# SMT_Nixie_Board_HV5622.net
KiCad netlist of a schematic drawn in EAGLE
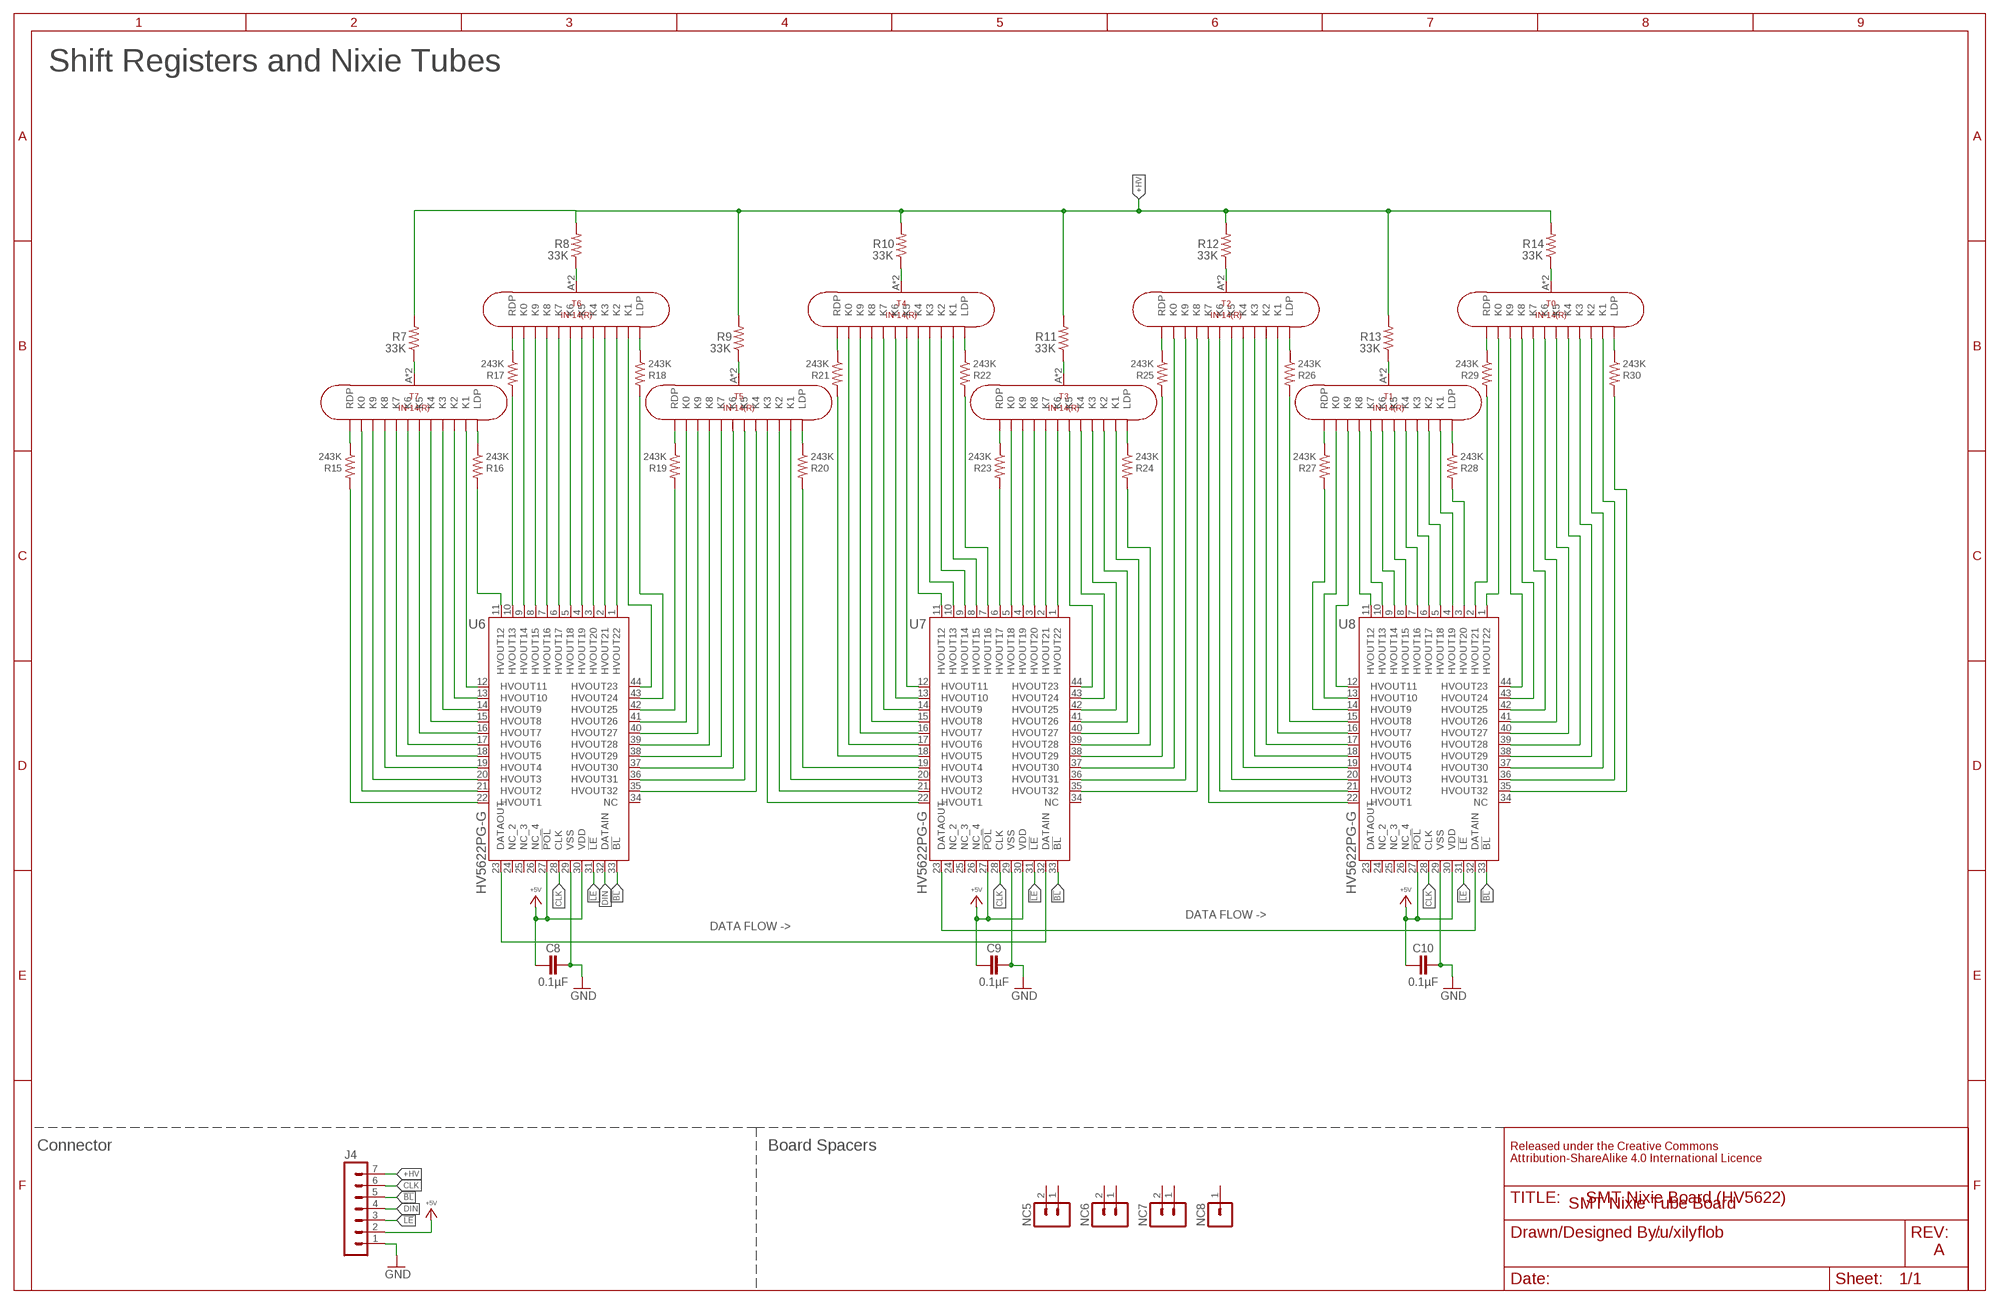
[diagram p0: schematic, sheet 1]

(export (version "E")
  (design (tool "Eeschema 10.0.6"))
  (components
    (comp (ref "C8")
      (value "0.1µF")
      (footprint "eagle-import:C0805")
      (libsource (lib "eagle-import") (part "C-EU"))
    )
    (comp (ref "C9")
      (value "0.1µF")
      (footprint "eagle-import:C0805")
      (libsource (lib "eagle-import") (part "C-EU"))
    )
    (comp (ref "C10")
      (value "0.1µF")
      (footprint "eagle-import:C0805")
      (libsource (lib "eagle-import") (part "C-EU"))
    )
    (comp (ref "J4")
      (value "1")
      (footprint "eagle-import:MA07")
      (libsource (lib "eagle-import") (part "MA07"))
    )
    (comp (ref "NC5")
      (value "MA02")
      (footprint "eagle-import:MA02")
      (libsource (lib "eagle-import") (part "MA02"))
    )
    (comp (ref "NC6")
      (value "MA02")
      (footprint "eagle-import:MA02")
      (libsource (lib "eagle-import") (part "MA02"))
    )
    (comp (ref "NC7")
      (value "MA02")
      (footprint "eagle-import:MA02")
      (libsource (lib "eagle-import") (part "MA02"))
    )
    (comp (ref "NC8")
      (value "MA01")
      (footprint "eagle-import:MA01")
      (libsource (lib "eagle-import") (part "MA01"))
    )
    (comp (ref "R7")
      (value "33K")
      (footprint "eagle-import:R2512")
      (libsource (lib "eagle-import") (part "R-US_R2512"))
    )
    (comp (ref "R8")
      (value "33K")
      (footprint "eagle-import:R2512")
      (libsource (lib "eagle-import") (part "R-US_R2512"))
    )
    (comp (ref "R9")
      (value "33K")
      (footprint "eagle-import:R2512")
      (libsource (lib "eagle-import") (part "R-US_R2512"))
    )
    (comp (ref "R10")
      (value "33K")
      (footprint "eagle-import:R2512")
      (libsource (lib "eagle-import") (part "R-US_R2512"))
    )
    (comp (ref "R11")
      (value "33K")
      (footprint "eagle-import:R2512")
      (libsource (lib "eagle-import") (part "R-US_R2512"))
    )
    (comp (ref "R12")
      (value "33K")
      (footprint "eagle-import:R2512")
      (libsource (lib "eagle-import") (part "R-US_R2512"))
    )
    (comp (ref "R13")
      (value "33K")
      (footprint "eagle-import:R2512")
      (libsource (lib "eagle-import") (part "R-US_R2512"))
    )
    (comp (ref "R14")
      (value "33K")
      (footprint "eagle-import:R2512")
      (libsource (lib "eagle-import") (part "R-US_R2512"))
    )
    (comp (ref "R15")
      (value "243K")
      (footprint "eagle-import:R2010")
      (libsource (lib "eagle-import") (part "R-US_R2010"))
    )
    (comp (ref "R16")
      (value "243K")
      (footprint "eagle-import:R2010")
      (libsource (lib "eagle-import") (part "R-US_R2010"))
    )
    (comp (ref "R17")
      (value "243K")
      (footprint "eagle-import:R2010")
      (libsource (lib "eagle-import") (part "R-US_R2010"))
    )
    (comp (ref "R18")
      (value "243K")
      (footprint "eagle-import:R2010")
      (libsource (lib "eagle-import") (part "R-US_R2010"))
    )
    (comp (ref "R19")
      (value "243K")
      (footprint "eagle-import:R2010")
      (libsource (lib "eagle-import") (part "R-US_R2010"))
    )
    (comp (ref "R20")
      (value "243K")
      (footprint "eagle-import:R2010")
      (libsource (lib "eagle-import") (part "R-US_R2010"))
    )
    (comp (ref "R21")
      (value "243K")
      (footprint "eagle-import:R2010")
      (libsource (lib "eagle-import") (part "R-US_R2010"))
    )
    (comp (ref "R22")
      (value "243K")
      (footprint "eagle-import:R2010")
      (libsource (lib "eagle-import") (part "R-US_R2010"))
    )
    (comp (ref "R23")
      (value "243K")
      (footprint "eagle-import:R2010")
      (libsource (lib "eagle-import") (part "R-US_R2010"))
    )
    (comp (ref "R24")
      (value "243K")
      (footprint "eagle-import:R2010")
      (libsource (lib "eagle-import") (part "R-US_R2010"))
    )
    (comp (ref "R25")
      (value "243K")
      (footprint "eagle-import:R2010")
      (libsource (lib "eagle-import") (part "R-US_R2010"))
    )
    (comp (ref "R26")
      (value "243K")
      (footprint "eagle-import:R2010")
      (libsource (lib "eagle-import") (part "R-US_R2010"))
    )
    (comp (ref "R27")
      (value "243K")
      (footprint "eagle-import:R2010")
      (libsource (lib "eagle-import") (part "R-US_R2010"))
    )
    (comp (ref "R28")
      (value "243K")
      (footprint "eagle-import:R2010")
      (libsource (lib "eagle-import") (part "R-US_R2010"))
    )
    (comp (ref "R29")
      (value "243K")
      (footprint "eagle-import:R2010")
      (libsource (lib "eagle-import") (part "R-US_R2010"))
    )
    (comp (ref "R30")
      (value "243K")
      (footprint "eagle-import:R2010")
      (libsource (lib "eagle-import") (part "R-US_R2010"))
    )
    (comp (ref "T0")
      (value "IN-14(R)")
      (footprint "eagle-import:IN-14_REVERSE")
      (libsource (lib "eagle-import") (part "IN-14(R)"))
    )
    (comp (ref "T1")
      (value "IN-14(R)")
      (footprint "eagle-import:IN-14_REVERSE")
      (libsource (lib "eagle-import") (part "IN-14(R)"))
    )
    (comp (ref "T2")
      (value "IN-14(R)")
      (footprint "eagle-import:IN-14_REVERSE")
      (libsource (lib "eagle-import") (part "IN-14(R)"))
    )
    (comp (ref "T3")
      (value "IN-14(R)")
      (footprint "eagle-import:IN-14_REVERSE")
      (libsource (lib "eagle-import") (part "IN-14(R)"))
    )
    (comp (ref "T4")
      (value "IN-14(R)")
      (footprint "eagle-import:IN-14_REVERSE")
      (libsource (lib "eagle-import") (part "IN-14(R)"))
    )
    (comp (ref "T5")
      (value "IN-14(R)")
      (footprint "eagle-import:IN-14_REVERSE")
      (libsource (lib "eagle-import") (part "IN-14(R)"))
    )
    (comp (ref "T6")
      (value "IN-14(R)")
      (footprint "eagle-import:IN-14_REVERSE")
      (libsource (lib "eagle-import") (part "IN-14(R)"))
    )
    (comp (ref "T7")
      (value "IN-14(R)")
      (footprint "eagle-import:IN-14_REVERSE")
      (libsource (lib "eagle-import") (part "IN-14(R)"))
    )
    (comp (ref "U6")
      (value "HV5622PG-G")
      (footprint "eagle-import:QFP-44")
      (fields (field (name "COPYRIGHT") "Copyright (C) 2018 Accelerated Designs. All rights reserved"))
      (libsource (lib "eagle-import") (part "HV5622PG-G"))
    )
    (comp (ref "U7")
      (value "HV5622PG-G")
      (footprint "eagle-import:QFP-44")
      (fields (field (name "COPYRIGHT") "Copyright (C) 2018 Accelerated Designs. All rights reserved"))
      (libsource (lib "eagle-import") (part "HV5622PG-G"))
    )
    (comp (ref "U8")
      (value "HV5622PG-G")
      (footprint "eagle-import:QFP-44")
      (fields (field (name "COPYRIGHT") "Copyright (C) 2018 Accelerated Designs. All rights reserved"))
      (libsource (lib "eagle-import") (part "HV5622PG-G"))
    )
  )
  (nets
    (net (code "1") (name "+5V") (class "Default")
      (node (ref "C10") (pin "1") (pinfunction "1_1") (pintype "passive"))
      (node (ref "C8") (pin "1") (pinfunction "1_1") (pintype "passive"))
      (node (ref "C9") (pin "1") (pinfunction "1_1") (pintype "passive"))
      (node (ref "J4") (pin "2") (pinfunction "2_2") (pintype "passive"))
      (node (ref "U6") (pin "27") (pinfunction "~{POL}_27") (pintype "passive"))
      (node (ref "U6") (pin "30") (pinfunction "VDD_30") (pintype "power_in"))
      (node (ref "U7") (pin "27") (pinfunction "~{POL}_27") (pintype "passive"))
      (node (ref "U7") (pin "30") (pinfunction "VDD_30") (pintype "power_in"))
      (node (ref "U8") (pin "27") (pinfunction "~{POL}_27") (pintype "passive"))
      (node (ref "U8") (pin "30") (pinfunction "VDD_30") (pintype "power_in"))
    )
    (net (code "2") (name "+HV") (class "Default")
      (node (ref "J4") (pin "7") (pinfunction "7_7") (pintype "passive"))
      (node (ref "R10") (pin "2") (pinfunction "2_2") (pintype "passive"))
      (node (ref "R11") (pin "2") (pinfunction "2_2") (pintype "passive"))
      (node (ref "R12") (pin "2") (pinfunction "2_2") (pintype "passive"))
      (node (ref "R13") (pin "2") (pinfunction "2_2") (pintype "passive"))
      (node (ref "R14") (pin "2") (pinfunction "2_2") (pintype "passive"))
      (node (ref "R7") (pin "2") (pinfunction "2_2") (pintype "passive"))
      (node (ref "R8") (pin "2") (pinfunction "2_2") (pintype "passive"))
      (node (ref "R9") (pin "2") (pinfunction "2_2") (pintype "passive"))
    )
    (net (code "3") (name "/~{BL}") (class "Default")
      (node (ref "J4") (pin "5") (pinfunction "5_5") (pintype "passive"))
      (node (ref "U6") (pin "33") (pinfunction "~{BL}_33") (pintype "passive"))
      (node (ref "U7") (pin "33") (pinfunction "~{BL}_33") (pintype "passive"))
      (node (ref "U8") (pin "33") (pinfunction "~{BL}_33") (pintype "passive"))
    )
    (net (code "4") (name "/~{LE}") (class "Default")
      (node (ref "J4") (pin "3") (pinfunction "3_3") (pintype "passive"))
      (node (ref "U6") (pin "31") (pinfunction "~{LE}_31") (pintype "input"))
      (node (ref "U7") (pin "31") (pinfunction "~{LE}_31") (pintype "input"))
      (node (ref "U8") (pin "31") (pinfunction "~{LE}_31") (pintype "input"))
    )
    (net (code "5") (name "CLK") (class "Default")
      (node (ref "J4") (pin "6") (pinfunction "6_6") (pintype "passive"))
      (node (ref "U6") (pin "28") (pinfunction "CLK_28") (pintype "input"))
      (node (ref "U7") (pin "28") (pinfunction "CLK_28") (pintype "input"))
      (node (ref "U8") (pin "28") (pinfunction "CLK_28") (pintype "input"))
    )
    (net (code "6") (name "DIN") (class "Default")
      (node (ref "J4") (pin "4") (pinfunction "4_4") (pintype "passive"))
      (node (ref "U6") (pin "32") (pinfunction "DATAIN_32") (pintype "input"))
    )
    (net (code "7") (name "GND") (class "Default")
      (node (ref "C10") (pin "2") (pinfunction "2_2") (pintype "passive"))
      (node (ref "C8") (pin "2") (pinfunction "2_2") (pintype "passive"))
      (node (ref "C9") (pin "2") (pinfunction "2_2") (pintype "passive"))
      (node (ref "J4") (pin "1") (pinfunction "1_1") (pintype "passive"))
      (node (ref "U6") (pin "29") (pinfunction "VSS_29") (pintype "power_in"))
      (node (ref "U7") (pin "29") (pinfunction "VSS_29") (pintype "power_in"))
      (node (ref "U8") (pin "29") (pinfunction "VSS_29") (pintype "power_in"))
    )
    (net (code "8") (name "Net-(R7-Pad1)") (class "Default")
      (node (ref "R7") (pin "1") (pinfunction "1_1") (pintype "passive"))
      (node (ref "T7") (pin "A") (pinfunction "A_A") (pintype "output"))
      (node (ref "T7") (pin "A_1") (pinfunction "A_A_1") (pintype "output"))
    )
    (net (code "9") (name "Net-(R8-Pad1)") (class "Default")
      (node (ref "R8") (pin "1") (pinfunction "1_1") (pintype "passive"))
      (node (ref "T6") (pin "A") (pinfunction "A_A") (pintype "output"))
      (node (ref "T6") (pin "A_1") (pinfunction "A_A_1") (pintype "output"))
    )
    (net (code "10") (name "Net-(R9-Pad1)") (class "Default")
      (node (ref "R9") (pin "1") (pinfunction "1_1") (pintype "passive"))
      (node (ref "T5") (pin "A") (pinfunction "A_A") (pintype "output"))
      (node (ref "T5") (pin "A_1") (pinfunction "A_A_1") (pintype "output"))
    )
    (net (code "11") (name "Net-(R10-Pad1)") (class "Default")
      (node (ref "R10") (pin "1") (pinfunction "1_1") (pintype "passive"))
      (node (ref "T4") (pin "A") (pinfunction "A_A") (pintype "output"))
      (node (ref "T4") (pin "A_1") (pinfunction "A_A_1") (pintype "output"))
    )
    (net (code "12") (name "Net-(R11-Pad1)") (class "Default")
      (node (ref "R11") (pin "1") (pinfunction "1_1") (pintype "passive"))
      (node (ref "T3") (pin "A") (pinfunction "A_A") (pintype "output"))
      (node (ref "T3") (pin "A_1") (pinfunction "A_A_1") (pintype "output"))
    )
    (net (code "13") (name "Net-(R12-Pad1)") (class "Default")
      (node (ref "R12") (pin "1") (pinfunction "1_1") (pintype "passive"))
      (node (ref "T2") (pin "A") (pinfunction "A_A") (pintype "output"))
      (node (ref "T2") (pin "A_1") (pinfunction "A_A_1") (pintype "output"))
    )
    (net (code "14") (name "Net-(R13-Pad1)") (class "Default")
      (node (ref "R13") (pin "1") (pinfunction "1_1") (pintype "passive"))
      (node (ref "T1") (pin "A") (pinfunction "A_A") (pintype "output"))
      (node (ref "T1") (pin "A_1") (pinfunction "A_A_1") (pintype "output"))
    )
    (net (code "15") (name "Net-(R14-Pad1)") (class "Default")
      (node (ref "R14") (pin "1") (pinfunction "1_1") (pintype "passive"))
      (node (ref "T0") (pin "A") (pinfunction "A_A") (pintype "output"))
      (node (ref "T0") (pin "A_1") (pinfunction "A_A_1") (pintype "output"))
    )
    (net (code "16") (name "Net-(R15-Pad1)") (class "Default")
      (node (ref "R15") (pin "1") (pinfunction "1_1") (pintype "passive"))
      (node (ref "T7") (pin "RDP") (pinfunction "RDP_RDP") (pintype "input"))
      (node (ref "T7") (pin "RDP_1") (pinfunction "RDP_RDP_1") (pintype "input"))
    )
    (net (code "17") (name "Net-(R16-Pad1)") (class "Default")
      (node (ref "R16") (pin "1") (pinfunction "1_1") (pintype "passive"))
      (node (ref "T7") (pin "LDP") (pinfunction "LDP_LDP") (pintype "input"))
      (node (ref "T7") (pin "LDP_1") (pinfunction "LDP_LDP_1") (pintype "input"))
    )
    (net (code "18") (name "Net-(R17-Pad1)") (class "Default")
      (node (ref "R17") (pin "1") (pinfunction "1_1") (pintype "passive"))
      (node (ref "T6") (pin "RDP") (pinfunction "RDP_RDP") (pintype "input"))
      (node (ref "T6") (pin "RDP_1") (pinfunction "RDP_RDP_1") (pintype "input"))
    )
    (net (code "19") (name "Net-(R18-Pad1)") (class "Default")
      (node (ref "R18") (pin "1") (pinfunction "1_1") (pintype "passive"))
      (node (ref "T6") (pin "LDP") (pinfunction "LDP_LDP") (pintype "input"))
      (node (ref "T6") (pin "LDP_1") (pinfunction "LDP_LDP_1") (pintype "input"))
    )
    (net (code "20") (name "Net-(R19-Pad1)") (class "Default")
      (node (ref "R19") (pin "1") (pinfunction "1_1") (pintype "passive"))
      (node (ref "T5") (pin "RDP") (pinfunction "RDP_RDP") (pintype "input"))
      (node (ref "T5") (pin "RDP_1") (pinfunction "RDP_RDP_1") (pintype "input"))
    )
    (net (code "21") (name "Net-(R20-Pad1)") (class "Default")
      (node (ref "R20") (pin "1") (pinfunction "1_1") (pintype "passive"))
      (node (ref "T5") (pin "LDP") (pinfunction "LDP_LDP") (pintype "input"))
      (node (ref "T5") (pin "LDP_1") (pinfunction "LDP_LDP_1") (pintype "input"))
    )
    (net (code "22") (name "Net-(R21-Pad1)") (class "Default")
      (node (ref "R21") (pin "1") (pinfunction "1_1") (pintype "passive"))
      (node (ref "T4") (pin "RDP") (pinfunction "RDP_RDP") (pintype "input"))
      (node (ref "T4") (pin "RDP_1") (pinfunction "RDP_RDP_1") (pintype "input"))
    )
    (net (code "23") (name "Net-(R22-Pad1)") (class "Default")
      (node (ref "R22") (pin "1") (pinfunction "1_1") (pintype "passive"))
      (node (ref "T4") (pin "LDP") (pinfunction "LDP_LDP") (pintype "input"))
      (node (ref "T4") (pin "LDP_1") (pinfunction "LDP_LDP_1") (pintype "input"))
    )
    (net (code "24") (name "Net-(R23-Pad1)") (class "Default")
      (node (ref "R23") (pin "1") (pinfunction "1_1") (pintype "passive"))
      (node (ref "T3") (pin "RDP") (pinfunction "RDP_RDP") (pintype "input"))
      (node (ref "T3") (pin "RDP_1") (pinfunction "RDP_RDP_1") (pintype "input"))
    )
    (net (code "25") (name "Net-(R24-Pad1)") (class "Default")
      (node (ref "R24") (pin "1") (pinfunction "1_1") (pintype "passive"))
      (node (ref "T3") (pin "LDP") (pinfunction "LDP_LDP") (pintype "input"))
      (node (ref "T3") (pin "LDP_1") (pinfunction "LDP_LDP_1") (pintype "input"))
    )
    (net (code "26") (name "Net-(R25-Pad1)") (class "Default")
      (node (ref "R25") (pin "1") (pinfunction "1_1") (pintype "passive"))
      (node (ref "T2") (pin "RDP") (pinfunction "RDP_RDP") (pintype "input"))
      (node (ref "T2") (pin "RDP_1") (pinfunction "RDP_RDP_1") (pintype "input"))
    )
    (net (code "27") (name "Net-(R26-Pad1)") (class "Default")
      (node (ref "R26") (pin "1") (pinfunction "1_1") (pintype "passive"))
      (node (ref "T2") (pin "LDP") (pinfunction "LDP_LDP") (pintype "input"))
      (node (ref "T2") (pin "LDP_1") (pinfunction "LDP_LDP_1") (pintype "input"))
    )
    (net (code "28") (name "Net-(R27-Pad1)") (class "Default")
      (node (ref "R27") (pin "1") (pinfunction "1_1") (pintype "passive"))
      (node (ref "T1") (pin "RDP") (pinfunction "RDP_RDP") (pintype "input"))
      (node (ref "T1") (pin "RDP_1") (pinfunction "RDP_RDP_1") (pintype "input"))
    )
    (net (code "29") (name "Net-(R28-Pad1)") (class "Default")
      (node (ref "R28") (pin "1") (pinfunction "1_1") (pintype "passive"))
      (node (ref "T1") (pin "LDP") (pinfunction "LDP_LDP") (pintype "input"))
      (node (ref "T1") (pin "LDP_1") (pinfunction "LDP_LDP_1") (pintype "input"))
    )
    (net (code "30") (name "Net-(R29-Pad1)") (class "Default")
      (node (ref "R29") (pin "1") (pinfunction "1_1") (pintype "passive"))
      (node (ref "T0") (pin "RDP") (pinfunction "RDP_RDP") (pintype "input"))
      (node (ref "T0") (pin "RDP_1") (pinfunction "RDP_RDP_1") (pintype "input"))
    )
    (net (code "31") (name "Net-(R30-Pad1)") (class "Default")
      (node (ref "R30") (pin "1") (pinfunction "1_1") (pintype "passive"))
      (node (ref "T0") (pin "LDP") (pinfunction "LDP_LDP") (pintype "input"))
      (node (ref "T0") (pin "LDP_1") (pinfunction "LDP_LDP_1") (pintype "input"))
    )
    (net (code "32") (name "Net-(U6-DATAOUT)") (class "Default")
      (node (ref "U6") (pin "23") (pinfunction "DATAOUT_23") (pintype "output"))
      (node (ref "U7") (pin "32") (pinfunction "DATAIN_32") (pintype "input"))
    )
    (net (code "33") (name "Net-(U6-HVOUT1)") (class "Default")
      (node (ref "R15") (pin "2") (pinfunction "2_2") (pintype "passive"))
      (node (ref "U6") (pin "22") (pinfunction "HVOUT1_22") (pintype "output"))
    )
    (net (code "34") (name "Net-(U6-HVOUT2)") (class "Default")
      (node (ref "T7") (pin "K0") (pinfunction "K0_K0") (pintype "input"))
      (node (ref "T7") (pin "K0_1") (pinfunction "K0_K0_1") (pintype "input"))
      (node (ref "U6") (pin "21") (pinfunction "HVOUT2_21") (pintype "output"))
    )
    (net (code "35") (name "Net-(U6-HVOUT3)") (class "Default")
      (node (ref "T7") (pin "K9") (pinfunction "K9_K9") (pintype "input"))
      (node (ref "T7") (pin "K9_1") (pinfunction "K9_K9_1") (pintype "input"))
      (node (ref "U6") (pin "20") (pinfunction "HVOUT3_20") (pintype "output"))
    )
    (net (code "36") (name "Net-(U6-HVOUT4)") (class "Default")
      (node (ref "T7") (pin "K8") (pinfunction "K8_K8") (pintype "input"))
      (node (ref "T7") (pin "K8_1") (pinfunction "K8_K8_1") (pintype "input"))
      (node (ref "U6") (pin "19") (pinfunction "HVOUT4_19") (pintype "output"))
    )
    (net (code "37") (name "Net-(U6-HVOUT5)") (class "Default")
      (node (ref "T7") (pin "K7") (pinfunction "K7_K7") (pintype "input"))
      (node (ref "T7") (pin "K7_1") (pinfunction "K7_K7_1") (pintype "input"))
      (node (ref "U6") (pin "18") (pinfunction "HVOUT5_18") (pintype "output"))
    )
    (net (code "38") (name "Net-(U6-HVOUT6)") (class "Default")
      (node (ref "T7") (pin "K6") (pinfunction "K6_K6") (pintype "input"))
      (node (ref "T7") (pin "K6_1") (pinfunction "K6_K6_1") (pintype "input"))
      (node (ref "U6") (pin "17") (pinfunction "HVOUT6_17") (pintype "output"))
    )
    (net (code "39") (name "Net-(U6-HVOUT7)") (class "Default")
      (node (ref "T7") (pin "K5") (pinfunction "K5_K5") (pintype "input"))
      (node (ref "T7") (pin "K5_1") (pinfunction "K5_K5_1") (pintype "input"))
      (node (ref "U6") (pin "16") (pinfunction "HVOUT7_16") (pintype "output"))
    )
    (net (code "40") (name "Net-(U6-HVOUT8)") (class "Default")
      (node (ref "T7") (pin "K4") (pinfunction "K4_K4") (pintype "input"))
      (node (ref "T7") (pin "K4_1") (pinfunction "K4_K4_1") (pintype "input"))
      (node (ref "U6") (pin "15") (pinfunction "HVOUT8_15") (pintype "output"))
    )
    (net (code "41") (name "Net-(U6-HVOUT9)") (class "Default")
      (node (ref "T7") (pin "K3") (pinfunction "K3_K3") (pintype "input"))
      (node (ref "T7") (pin "K3_1") (pinfunction "K3_K3_1") (pintype "input"))
      (node (ref "U6") (pin "14") (pinfunction "HVOUT9_14") (pintype "output"))
    )
    (net (code "42") (name "Net-(U6-HVOUT10)") (class "Default")
      (node (ref "T7") (pin "K2") (pinfunction "K2_K2") (pintype "input"))
      (node (ref "T7") (pin "K2_1") (pinfunction "K2_K2_1") (pintype "input"))
      (node (ref "U6") (pin "13") (pinfunction "HVOUT10_13") (pintype "output"))
    )
    (net (code "43") (name "Net-(U6-HVOUT11)") (class "Default")
      (node (ref "T7") (pin "K1") (pinfunction "K1_K1") (pintype "input"))
      (node (ref "T7") (pin "K1_1") (pinfunction "K1_K1_1") (pintype "input"))
      (node (ref "U6") (pin "12") (pinfunction "HVOUT11_12") (pintype "output"))
    )
    (net (code "44") (name "Net-(U6-HVOUT12)") (class "Default")
      (node (ref "R16") (pin "2") (pinfunction "2_2") (pintype "passive"))
      (node (ref "U6") (pin "11") (pinfunction "HVOUT12_11") (pintype "output"))
    )
    (net (code "45") (name "Net-(U6-HVOUT13)") (class "Default")
      (node (ref "R17") (pin "2") (pinfunction "2_2") (pintype "passive"))
      (node (ref "U6") (pin "10") (pinfunction "HVOUT13_10") (pintype "output"))
    )
    (net (code "46") (name "Net-(U6-HVOUT14)") (class "Default")
      (node (ref "T6") (pin "K0") (pinfunction "K0_K0") (pintype "input"))
      (node (ref "T6") (pin "K0_1") (pinfunction "K0_K0_1") (pintype "input"))
      (node (ref "U6") (pin "9") (pinfunction "HVOUT14_9") (pintype "output"))
    )
    (net (code "47") (name "Net-(U6-HVOUT15)") (class "Default")
      (node (ref "T6") (pin "K9") (pinfunction "K9_K9") (pintype "input"))
      (node (ref "T6") (pin "K9_1") (pinfunction "K9_K9_1") (pintype "input"))
      (node (ref "U6") (pin "8") (pinfunction "HVOUT15_8") (pintype "output"))
    )
    (net (code "48") (name "Net-(U6-HVOUT16)") (class "Default")
      (node (ref "T6") (pin "K8") (pinfunction "K8_K8") (pintype "input"))
      (node (ref "T6") (pin "K8_1") (pinfunction "K8_K8_1") (pintype "input"))
      (node (ref "U6") (pin "7") (pinfunction "HVOUT16_7") (pintype "output"))
    )
    (net (code "49") (name "Net-(U6-HVOUT17)") (class "Default")
      (node (ref "T6") (pin "K7") (pinfunction "K7_K7") (pintype "input"))
      (node (ref "T6") (pin "K7_1") (pinfunction "K7_K7_1") (pintype "input"))
      (node (ref "U6") (pin "6") (pinfunction "HVOUT17_6") (pintype "output"))
    )
    (net (code "50") (name "Net-(U6-HVOUT18)") (class "Default")
      (node (ref "T6") (pin "K6") (pinfunction "K6_K6") (pintype "input"))
      (node (ref "T6") (pin "K6_1") (pinfunction "K6_K6_1") (pintype "input"))
      (node (ref "U6") (pin "5") (pinfunction "HVOUT18_5") (pintype "output"))
    )
    (net (code "51") (name "Net-(U6-HVOUT19)") (class "Default")
      (node (ref "T6") (pin "K5") (pinfunction "K5_K5") (pintype "input"))
      (node (ref "T6") (pin "K5_1") (pinfunction "K5_K5_1") (pintype "input"))
      (node (ref "U6") (pin "4") (pinfunction "HVOUT19_4") (pintype "output"))
    )
    (net (code "52") (name "Net-(U6-HVOUT20)") (class "Default")
      (node (ref "T6") (pin "K4") (pinfunction "K4_K4") (pintype "input"))
      (node (ref "T6") (pin "K4_1") (pinfunction "K4_K4_1") (pintype "input"))
      (node (ref "U6") (pin "3") (pinfunction "HVOUT20_3") (pintype "output"))
    )
    (net (code "53") (name "Net-(U6-HVOUT21)") (class "Default")
      (node (ref "T6") (pin "K3") (pinfunction "K3_K3") (pintype "input"))
      (node (ref "T6") (pin "K3_1") (pinfunction "K3_K3_1") (pintype "input"))
      (node (ref "U6") (pin "2") (pinfunction "HVOUT21_2") (pintype "output"))
    )
    (net (code "54") (name "Net-(U6-HVOUT22)") (class "Default")
      (node (ref "T6") (pin "K2") (pinfunction "K2_K2") (pintype "input"))
      (node (ref "T6") (pin "K2_1") (pinfunction "K2_K2_1") (pintype "input"))
      (node (ref "U6") (pin "1") (pinfunction "HVOUT22_1") (pintype "output"))
    )
    (net (code "55") (name "Net-(U6-HVOUT23)") (class "Default")
      (node (ref "T6") (pin "K1") (pinfunction "K1_K1") (pintype "input"))
      (node (ref "T6") (pin "K1_1") (pinfunction "K1_K1_1") (pintype "input"))
      (node (ref "U6") (pin "44") (pinfunction "HVOUT23_44") (pintype "output"))
    )
    (net (code "56") (name "Net-(U6-HVOUT24)") (class "Default")
      (node (ref "R18") (pin "2") (pinfunction "2_2") (pintype "passive"))
      (node (ref "U6") (pin "43") (pinfunction "HVOUT24_43") (pintype "output"))
    )
    (net (code "57") (name "Net-(U6-HVOUT25)") (class "Default")
      (node (ref "R19") (pin "2") (pinfunction "2_2") (pintype "passive"))
      (node (ref "U6") (pin "42") (pinfunction "HVOUT25_42") (pintype "output"))
    )
    (net (code "58") (name "Net-(U6-HVOUT26)") (class "Default")
      (node (ref "T5") (pin "K0") (pinfunction "K0_K0") (pintype "input"))
      (node (ref "T5") (pin "K0_1") (pinfunction "K0_K0_1") (pintype "input"))
      (node (ref "U6") (pin "41") (pinfunction "HVOUT26_41") (pintype "output"))
    )
    (net (code "59") (name "Net-(U6-HVOUT27)") (class "Default")
      (node (ref "T5") (pin "K9") (pinfunction "K9_K9") (pintype "input"))
      (node (ref "T5") (pin "K9_1") (pinfunction "K9_K9_1") (pintype "input"))
      (node (ref "U6") (pin "40") (pinfunction "HVOUT27_40") (pintype "output"))
    )
    (net (code "60") (name "Net-(U6-HVOUT28)") (class "Default")
      (node (ref "T5") (pin "K8") (pinfunction "K8_K8") (pintype "input"))
      (node (ref "T5") (pin "K8_1") (pinfunction "K8_K8_1") (pintype "input"))
      (node (ref "U6") (pin "39") (pinfunction "HVOUT28_39") (pintype "output"))
    )
    (net (code "61") (name "Net-(U6-HVOUT29)") (class "Default")
      (node (ref "T5") (pin "K7") (pinfunction "K7_K7") (pintype "input"))
      (node (ref "T5") (pin "K7_1") (pinfunction "K7_K7_1") (pintype "input"))
      (node (ref "U6") (pin "38") (pinfunction "HVOUT29_38") (pintype "output"))
    )
    (net (code "62") (name "Net-(U6-HVOUT30)") (class "Default")
      (node (ref "T5") (pin "K6") (pinfunction "K6_K6") (pintype "input"))
      (node (ref "T5") (pin "K6_1") (pinfunction "K6_K6_1") (pintype "input"))
      (node (ref "U6") (pin "37") (pinfunction "HVOUT30_37") (pintype "output"))
    )
    (net (code "63") (name "Net-(U6-HVOUT31)") (class "Default")
      (node (ref "T5") (pin "K5") (pinfunction "K5_K5") (pintype "input"))
      (node (ref "T5") (pin "K5_1") (pinfunction "K5_K5_1") (pintype "input"))
      (node (ref "U6") (pin "36") (pinfunction "HVOUT31_36") (pintype "output"))
    )
    (net (code "64") (name "Net-(U6-HVOUT32)") (class "Default")
      (node (ref "T5") (pin "K4") (pinfunction "K4_K4") (pintype "input"))
      (node (ref "T5") (pin "K4_1") (pinfunction "K4_K4_1") (pintype "input"))
      (node (ref "U6") (pin "35") (pinfunction "HVOUT32_35") (pintype "output"))
    )
    (net (code "65") (name "Net-(U7-DATAOUT)") (class "Default")
      (node (ref "U7") (pin "23") (pinfunction "DATAOUT_23") (pintype "output"))
      (node (ref "U8") (pin "32") (pinfunction "DATAIN_32") (pintype "input"))
    )
    (net (code "66") (name "Net-(U7-HVOUT1)") (class "Default")
      (node (ref "T5") (pin "K3") (pinfunction "K3_K3") (pintype "input"))
      (node (ref "T5") (pin "K3_1") (pinfunction "K3_K3_1") (pintype "input"))
      (node (ref "U7") (pin "22") (pinfunction "HVOUT1_22") (pintype "output"))
    )
    (net (code "67") (name "Net-(U7-HVOUT2)") (class "Default")
      (node (ref "T5") (pin "K2") (pinfunction "K2_K2") (pintype "input"))
      (node (ref "T5") (pin "K2_1") (pinfunction "K2_K2_1") (pintype "input"))
      (node (ref "U7") (pin "21") (pinfunction "HVOUT2_21") (pintype "output"))
    )
    (net (code "68") (name "Net-(U7-HVOUT3)") (class "Default")
      (node (ref "T5") (pin "K1") (pinfunction "K1_K1") (pintype "input"))
      (node (ref "T5") (pin "K1_1") (pinfunction "K1_K1_1") (pintype "input"))
      (node (ref "U7") (pin "20") (pinfunction "HVOUT3_20") (pintype "output"))
    )
    (net (code "69") (name "Net-(U7-HVOUT4)") (class "Default")
      (node (ref "R20") (pin "2") (pinfunction "2_2") (pintype "passive"))
      (node (ref "U7") (pin "19") (pinfunction "HVOUT4_19") (pintype "output"))
    )
    (net (code "70") (name "Net-(U7-HVOUT5)") (class "Default")
      (node (ref "R21") (pin "2") (pinfunction "2_2") (pintype "passive"))
      (node (ref "U7") (pin "18") (pinfunction "HVOUT5_18") (pintype "output"))
    )
    (net (code "71") (name "Net-(U7-HVOUT6)") (class "Default")
      (node (ref "T4") (pin "K0") (pinfunction "K0_K0") (pintype "input"))
      (node (ref "T4") (pin "K0_1") (pinfunction "K0_K0_1") (pintype "input"))
      (node (ref "U7") (pin "17") (pinfunction "HVOUT6_17") (pintype "output"))
    )
    (net (code "72") (name "Net-(U7-HVOUT7)") (class "Default")
      (node (ref "T4") (pin "K9") (pinfunction "K9_K9") (pintype "input"))
      (node (ref "T4") (pin "K9_1") (pinfunction "K9_K9_1") (pintype "input"))
      (node (ref "U7") (pin "16") (pinfunction "HVOUT7_16") (pintype "output"))
    )
    (net (code "73") (name "Net-(U7-HVOUT8)") (class "Default")
      (node (ref "T4") (pin "K8") (pinfunction "K8_K8") (pintype "input"))
      (node (ref "T4") (pin "K8_1") (pinfunction "K8_K8_1") (pintype "input"))
      (node (ref "U7") (pin "15") (pinfunction "HVOUT8_15") (pintype "output"))
    )
    (net (code "74") (name "Net-(U7-HVOUT9)") (class "Default")
      (node (ref "T4") (pin "K7") (pinfunction "K7_K7") (pintype "input"))
      (node (ref "T4") (pin "K7_1") (pinfunction "K7_K7_1") (pintype "input"))
      (node (ref "U7") (pin "14") (pinfunction "HVOUT9_14") (pintype "output"))
    )
    (net (code "75") (name "Net-(U7-HVOUT10)") (class "Default")
      (node (ref "T4") (pin "K6") (pinfunction "K6_K6") (pintype "input"))
      (node (ref "T4") (pin "K6_1") (pinfunction "K6_K6_1") (pintype "input"))
      (node (ref "U7") (pin "13") (pinfunction "HVOUT10_13") (pintype "output"))
    )
    (net (code "76") (name "Net-(U7-HVOUT11)") (class "Default")
      (node (ref "T4") (pin "K5") (pinfunction "K5_K5") (pintype "input"))
      (node (ref "T4") (pin "K5_1") (pinfunction "K5_K5_1") (pintype "input"))
      (node (ref "U7") (pin "12") (pinfunction "HVOUT11_12") (pintype "output"))
    )
    (net (code "77") (name "Net-(U7-HVOUT12)") (class "Default")
      (node (ref "T4") (pin "K4") (pinfunction "K4_K4") (pintype "input"))
      (node (ref "T4") (pin "K4_1") (pinfunction "K4_K4_1") (pintype "input"))
      (node (ref "U7") (pin "11") (pinfunction "HVOUT12_11") (pintype "output"))
    )
    (net (code "78") (name "Net-(U7-HVOUT13)") (class "Default")
      (node (ref "T4") (pin "K3") (pinfunction "K3_K3") (pintype "input"))
      (node (ref "T4") (pin "K3_1") (pinfunction "K3_K3_1") (pintype "input"))
      (node (ref "U7") (pin "10") (pinfunction "HVOUT13_10") (pintype "output"))
    )
    (net (code "79") (name "Net-(U7-HVOUT14)") (class "Default")
      (node (ref "T4") (pin "K2") (pinfunction "K2_K2") (pintype "input"))
      (node (ref "T4") (pin "K2_1") (pinfunction "K2_K2_1") (pintype "input"))
      (node (ref "U7") (pin "9") (pinfunction "HVOUT14_9") (pintype "output"))
    )
    (net (code "80") (name "Net-(U7-HVOUT15)") (class "Default")
      (node (ref "T4") (pin "K1") (pinfunction "K1_K1") (pintype "input"))
      (node (ref "T4") (pin "K1_1") (pinfunction "K1_K1_1") (pintype "input"))
      (node (ref "U7") (pin "8") (pinfunction "HVOUT15_8") (pintype "output"))
    )
    (net (code "81") (name "Net-(U7-HVOUT16)") (class "Default")
      (node (ref "R22") (pin "2") (pinfunction "2_2") (pintype "passive"))
      (node (ref "U7") (pin "7") (pinfunction "HVOUT16_7") (pintype "output"))
    )
    (net (code "82") (name "Net-(U7-HVOUT17)") (class "Default")
      (node (ref "R23") (pin "2") (pinfunction "2_2") (pintype "passive"))
      (node (ref "U7") (pin "6") (pinfunction "HVOUT17_6") (pintype "output"))
    )
    (net (code "83") (name "Net-(U7-HVOUT18)") (class "Default")
      (node (ref "T3") (pin "K0") (pinfunction "K0_K0") (pintype "input"))
      (node (ref "T3") (pin "K0_1") (pinfunction "K0_K0_1") (pintype "input"))
      (node (ref "U7") (pin "5") (pinfunction "HVOUT18_5") (pintype "output"))
    )
    (net (code "84") (name "Net-(U7-HVOUT19)") (class "Default")
      (node (ref "T3") (pin "K9") (pinfunction "K9_K9") (pintype "input"))
      (node (ref "T3") (pin "K9_1") (pinfunction "K9_K9_1") (pintype "input"))
      (node (ref "U7") (pin "4") (pinfunction "HVOUT19_4") (pintype "output"))
    )
    (net (code "85") (name "Net-(U7-HVOUT20)") (class "Default")
      (node (ref "T3") (pin "K8") (pinfunction "K8_K8") (pintype "input"))
      (node (ref "T3") (pin "K8_1") (pinfunction "K8_K8_1") (pintype "input"))
      (node (ref "U7") (pin "3") (pinfunction "HVOUT20_3") (pintype "output"))
    )
    (net (code "86") (name "Net-(U7-HVOUT21)") (class "Default")
      (node (ref "T3") (pin "K7") (pinfunction "K7_K7") (pintype "input"))
      (node (ref "T3") (pin "K7_1") (pinfunction "K7_K7_1") (pintype "input"))
      (node (ref "U7") (pin "2") (pinfunction "HVOUT21_2") (pintype "output"))
    )
    (net (code "87") (name "Net-(U7-HVOUT22)") (class "Default")
      (node (ref "T3") (pin "K6") (pinfunction "K6_K6") (pintype "input"))
      (node (ref "T3") (pin "K6_1") (pinfunction "K6_K6_1") (pintype "input"))
      (node (ref "U7") (pin "1") (pinfunction "HVOUT22_1") (pintype "output"))
    )
    (net (code "88") (name "Net-(U7-HVOUT23)") (class "Default")
      (node (ref "T3") (pin "K5") (pinfunction "K5_K5") (pintype "input"))
      (node (ref "T3") (pin "K5_1") (pinfunction "K5_K5_1") (pintype "input"))
      (node (ref "U7") (pin "44") (pinfunction "HVOUT23_44") (pintype "output"))
    )
    (net (code "89") (name "Net-(U7-HVOUT24)") (class "Default")
      (node (ref "T3") (pin "K4") (pinfunction "K4_K4") (pintype "input"))
      (node (ref "T3") (pin "K4_1") (pinfunction "K4_K4_1") (pintype "input"))
      (node (ref "U7") (pin "43") (pinfunction "HVOUT24_43") (pintype "output"))
    )
    (net (code "90") (name "Net-(U7-HVOUT25)") (class "Default")
      (node (ref "T3") (pin "K3") (pinfunction "K3_K3") (pintype "input"))
      (node (ref "T3") (pin "K3_1") (pinfunction "K3_K3_1") (pintype "input"))
      (node (ref "U7") (pin "42") (pinfunction "HVOUT25_42") (pintype "output"))
    )
    (net (code "91") (name "Net-(U7-HVOUT26)") (class "Default")
      (node (ref "T3") (pin "K2") (pinfunction "K2_K2") (pintype "input"))
      (node (ref "T3") (pin "K2_1") (pinfunction "K2_K2_1") (pintype "input"))
      (node (ref "U7") (pin "41") (pinfunction "HVOUT26_41") (pintype "output"))
    )
    (net (code "92") (name "Net-(U7-HVOUT27)") (class "Default")
      (node (ref "T3") (pin "K1") (pinfunction "K1_K1") (pintype "input"))
      (node (ref "T3") (pin "K1_1") (pinfunction "K1_K1_1") (pintype "input"))
      (node (ref "U7") (pin "40") (pinfunction "HVOUT27_40") (pintype "output"))
    )
    (net (code "93") (name "Net-(U7-HVOUT28)") (class "Default")
      (node (ref "R24") (pin "2") (pinfunction "2_2") (pintype "passive"))
      (node (ref "U7") (pin "39") (pinfunction "HVOUT28_39") (pintype "output"))
    )
    (net (code "94") (name "Net-(U7-HVOUT29)") (class "Default")
      (node (ref "R25") (pin "2") (pinfunction "2_2") (pintype "passive"))
      (node (ref "U7") (pin "38") (pinfunction "HVOUT29_38") (pintype "output"))
    )
    (net (code "95") (name "Net-(U7-HVOUT30)") (class "Default")
      (node (ref "T2") (pin "K0") (pinfunction "K0_K0") (pintype "input"))
      (node (ref "T2") (pin "K0_1") (pinfunction "K0_K0_1") (pintype "input"))
      (node (ref "U7") (pin "37") (pinfunction "HVOUT30_37") (pintype "output"))
    )
    (net (code "96") (name "Net-(U7-HVOUT31)") (class "Default")
      (node (ref "T2") (pin "K9") (pinfunction "K9_K9") (pintype "input"))
      (node (ref "T2") (pin "K9_1") (pinfunction "K9_K9_1") (pintype "input"))
      (node (ref "U7") (pin "36") (pinfunction "HVOUT31_36") (pintype "output"))
    )
    (net (code "97") (name "Net-(U7-HVOUT32)") (class "Default")
      (node (ref "T2") (pin "K8") (pinfunction "K8_K8") (pintype "input"))
      (node (ref "T2") (pin "K8_1") (pinfunction "K8_K8_1") (pintype "input"))
      (node (ref "U7") (pin "35") (pinfunction "HVOUT32_35") (pintype "output"))
    )
    (net (code "98") (name "Net-(U8-HVOUT1)") (class "Default")
      (node (ref "T2") (pin "K7") (pinfunction "K7_K7") (pintype "input"))
      (node (ref "T2") (pin "K7_1") (pinfunction "K7_K7_1") (pintype "input"))
      (node (ref "U8") (pin "22") (pinfunction "HVOUT1_22") (pintype "output"))
    )
    (net (code "99") (name "Net-(U8-HVOUT2)") (class "Default")
      (node (ref "T2") (pin "K6") (pinfunction "K6_K6") (pintype "input"))
      (node (ref "T2") (pin "K6_1") (pinfunction "K6_K6_1") (pintype "input"))
      (node (ref "U8") (pin "21") (pinfunction "HVOUT2_21") (pintype "output"))
    )
    (net (code "100") (name "Net-(U8-HVOUT3)") (class "Default")
      (node (ref "T2") (pin "K5") (pinfunction "K5_K5") (pintype "input"))
      (node (ref "T2") (pin "K5_1") (pinfunction "K5_K5_1") (pintype "input"))
      (node (ref "U8") (pin "20") (pinfunction "HVOUT3_20") (pintype "output"))
    )
    (net (code "101") (name "Net-(U8-HVOUT4)") (class "Default")
      (node (ref "T2") (pin "K4") (pinfunction "K4_K4") (pintype "input"))
      (node (ref "T2") (pin "K4_1") (pinfunction "K4_K4_1") (pintype "input"))
      (node (ref "U8") (pin "19") (pinfunction "HVOUT4_19") (pintype "output"))
    )
    (net (code "102") (name "Net-(U8-HVOUT5)") (class "Default")
      (node (ref "T2") (pin "K3") (pinfunction "K3_K3") (pintype "input"))
      (node (ref "T2") (pin "K3_1") (pinfunction "K3_K3_1") (pintype "input"))
      (node (ref "U8") (pin "18") (pinfunction "HVOUT5_18") (pintype "output"))
    )
    (net (code "103") (name "Net-(U8-HVOUT6)") (class "Default")
      (node (ref "T2") (pin "K2") (pinfunction "K2_K2") (pintype "input"))
      (node (ref "T2") (pin "K2_1") (pinfunction "K2_K2_1") (pintype "input"))
      (node (ref "U8") (pin "17") (pinfunction "HVOUT6_17") (pintype "output"))
    )
    (net (code "104") (name "Net-(U8-HVOUT7)") (class "Default")
      (node (ref "T2") (pin "K1") (pinfunction "K1_K1") (pintype "input"))
      (node (ref "T2") (pin "K1_1") (pinfunction "K1_K1_1") (pintype "input"))
      (node (ref "U8") (pin "16") (pinfunction "HVOUT7_16") (pintype "output"))
    )
    (net (code "105") (name "Net-(U8-HVOUT8)") (class "Default")
      (node (ref "R26") (pin "2") (pinfunction "2_2") (pintype "passive"))
      (node (ref "U8") (pin "15") (pinfunction "HVOUT8_15") (pintype "output"))
    )
    (net (code "106") (name "Net-(U8-HVOUT9)") (class "Default")
      (node (ref "R27") (pin "2") (pinfunction "2_2") (pintype "passive"))
      (node (ref "U8") (pin "14") (pinfunction "HVOUT9_14") (pintype "output"))
    )
    (net (code "107") (name "Net-(U8-HVOUT10)") (class "Default")
      (node (ref "T1") (pin "K0") (pinfunction "K0_K0") (pintype "input"))
      (node (ref "T1") (pin "K0_1") (pinfunction "K0_K0_1") (pintype "input"))
      (node (ref "U8") (pin "13") (pinfunction "HVOUT10_13") (pintype "output"))
    )
    (net (code "108") (name "Net-(U8-HVOUT11)") (class "Default")
      (node (ref "T1") (pin "K9") (pinfunction "K9_K9") (pintype "input"))
      (node (ref "T1") (pin "K9_1") (pinfunction "K9_K9_1") (pintype "input"))
      (node (ref "U8") (pin "12") (pinfunction "HVOUT11_12") (pintype "output"))
    )
    (net (code "109") (name "Net-(U8-HVOUT12)") (class "Default")
      (node (ref "T1") (pin "K8") (pinfunction "K8_K8") (pintype "input"))
      (node (ref "T1") (pin "K8_1") (pinfunction "K8_K8_1") (pintype "input"))
      (node (ref "U8") (pin "11") (pinfunction "HVOUT12_11") (pintype "output"))
    )
    (net (code "110") (name "Net-(U8-HVOUT13)") (class "Default")
      (node (ref "T1") (pin "K7") (pinfunction "K7_K7") (pintype "input"))
      (node (ref "T1") (pin "K7_1") (pinfunction "K7_K7_1") (pintype "input"))
      (node (ref "U8") (pin "10") (pinfunction "HVOUT13_10") (pintype "output"))
    )
    (net (code "111") (name "Net-(U8-HVOUT14)") (class "Default")
      (node (ref "T1") (pin "K6") (pinfunction "K6_K6") (pintype "input"))
      (node (ref "T1") (pin "K6_1") (pinfunction "K6_K6_1") (pintype "input"))
      (node (ref "U8") (pin "9") (pinfunction "HVOUT14_9") (pintype "output"))
    )
    (net (code "112") (name "Net-(U8-HVOUT15)") (class "Default")
      (node (ref "T1") (pin "K5") (pinfunction "K5_K5") (pintype "input"))
      (node (ref "T1") (pin "K5_1") (pinfunction "K5_K5_1") (pintype "input"))
      (node (ref "U8") (pin "8") (pinfunction "HVOUT15_8") (pintype "output"))
    )
    (net (code "113") (name "Net-(U8-HVOUT16)") (class "Default")
      (node (ref "T1") (pin "K4") (pinfunction "K4_K4") (pintype "input"))
      (node (ref "T1") (pin "K4_1") (pinfunction "K4_K4_1") (pintype "input"))
      (node (ref "U8") (pin "7") (pinfunction "HVOUT16_7") (pintype "output"))
    )
    (net (code "114") (name "Net-(U8-HVOUT17)") (class "Default")
      (node (ref "T1") (pin "K3") (pinfunction "K3_K3") (pintype "input"))
      (node (ref "T1") (pin "K3_1") (pinfunction "K3_K3_1") (pintype "input"))
      (node (ref "U8") (pin "6") (pinfunction "HVOUT17_6") (pintype "output"))
    )
    (net (code "115") (name "Net-(U8-HVOUT18)") (class "Default")
      (node (ref "T1") (pin "K2") (pinfunction "K2_K2") (pintype "input"))
      (node (ref "T1") (pin "K2_1") (pinfunction "K2_K2_1") (pintype "input"))
      (node (ref "U8") (pin "5") (pinfunction "HVOUT18_5") (pintype "output"))
    )
    (net (code "116") (name "Net-(U8-HVOUT19)") (class "Default")
      (node (ref "T1") (pin "K1") (pinfunction "K1_K1") (pintype "input"))
      (node (ref "T1") (pin "K1_1") (pinfunction "K1_K1_1") (pintype "input"))
      (node (ref "U8") (pin "4") (pinfunction "HVOUT19_4") (pintype "output"))
    )
    (net (code "117") (name "Net-(U8-HVOUT20)") (class "Default")
      (node (ref "R28") (pin "2") (pinfunction "2_2") (pintype "passive"))
      (node (ref "U8") (pin "3") (pinfunction "HVOUT20_3") (pintype "output"))
    )
    (net (code "118") (name "Net-(U8-HVOUT21)") (class "Default")
      (node (ref "R29") (pin "2") (pinfunction "2_2") (pintype "passive"))
      (node (ref "U8") (pin "2") (pinfunction "HVOUT21_2") (pintype "output"))
    )
    (net (code "119") (name "Net-(U8-HVOUT22)") (class "Default")
      (node (ref "T0") (pin "K0") (pinfunction "K0_K0") (pintype "input"))
      (node (ref "T0") (pin "K0_1") (pinfunction "K0_K0_1") (pintype "input"))
      (node (ref "U8") (pin "1") (pinfunction "HVOUT22_1") (pintype "output"))
    )
    (net (code "120") (name "Net-(U8-HVOUT23)") (class "Default")
      (node (ref "T0") (pin "K9") (pinfunction "K9_K9") (pintype "input"))
      (node (ref "T0") (pin "K9_1") (pinfunction "K9_K9_1") (pintype "input"))
      (node (ref "U8") (pin "44") (pinfunction "HVOUT23_44") (pintype "output"))
    )
    (net (code "121") (name "Net-(U8-HVOUT24)") (class "Default")
      (node (ref "T0") (pin "K8") (pinfunction "K8_K8") (pintype "input"))
      (node (ref "T0") (pin "K8_1") (pinfunction "K8_K8_1") (pintype "input"))
      (node (ref "U8") (pin "43") (pinfunction "HVOUT24_43") (pintype "output"))
    )
    (net (code "122") (name "Net-(U8-HVOUT25)") (class "Default")
      (node (ref "T0") (pin "K7") (pinfunction "K7_K7") (pintype "input"))
      (node (ref "T0") (pin "K7_1") (pinfunction "K7_K7_1") (pintype "input"))
      (node (ref "U8") (pin "42") (pinfunction "HVOUT25_42") (pintype "output"))
    )
    (net (code "123") (name "Net-(U8-HVOUT26)") (class "Default")
      (node (ref "T0") (pin "K6") (pinfunction "K6_K6") (pintype "input"))
      (node (ref "T0") (pin "K6_1") (pinfunction "K6_K6_1") (pintype "input"))
      (node (ref "U8") (pin "41") (pinfunction "HVOUT26_41") (pintype "output"))
    )
    (net (code "124") (name "Net-(U8-HVOUT27)") (class "Default")
      (node (ref "T0") (pin "K5") (pinfunction "K5_K5") (pintype "input"))
      (node (ref "T0") (pin "K5_1") (pinfunction "K5_K5_1") (pintype "input"))
      (node (ref "U8") (pin "40") (pinfunction "HVOUT27_40") (pintype "output"))
    )
    (net (code "125") (name "Net-(U8-HVOUT28)") (class "Default")
      (node (ref "T0") (pin "K4") (pinfunction "K4_K4") (pintype "input"))
      (node (ref "T0") (pin "K4_1") (pinfunction "K4_K4_1") (pintype "input"))
      (node (ref "U8") (pin "39") (pinfunction "HVOUT28_39") (pintype "output"))
    )
    (net (code "126") (name "Net-(U8-HVOUT29)") (class "Default")
      (node (ref "T0") (pin "K3") (pinfunction "K3_K3") (pintype "input"))
      (node (ref "T0") (pin "K3_1") (pinfunction "K3_K3_1") (pintype "input"))
      (node (ref "U8") (pin "38") (pinfunction "HVOUT29_38") (pintype "output"))
    )
    (net (code "127") (name "Net-(U8-HVOUT30)") (class "Default")
      (node (ref "T0") (pin "K2") (pinfunction "K2_K2") (pintype "input"))
      (node (ref "T0") (pin "K2_1") (pinfunction "K2_K2_1") (pintype "input"))
      (node (ref "U8") (pin "37") (pinfunction "HVOUT30_37") (pintype "output"))
    )
    (net (code "128") (name "Net-(U8-HVOUT31)") (class "Default")
      (node (ref "T0") (pin "K1") (pinfunction "K1_K1") (pintype "input"))
      (node (ref "T0") (pin "K1_1") (pinfunction "K1_K1_1") (pintype "input"))
      (node (ref "U8") (pin "36") (pinfunction "HVOUT31_36") (pintype "output"))
    )
    (net (code "129") (name "Net-(U8-HVOUT32)") (class "Default")
      (node (ref "R30") (pin "2") (pinfunction "2_2") (pintype "passive"))
      (node (ref "U8") (pin "35") (pinfunction "HVOUT32_35") (pintype "output"))
    )
    (net (code "130") (name "unconnected-(NC5-Pad1)") (class "Default")
      (node (ref "NC5") (pin "1") (pinfunction "1_1") (pintype "passive"))
    )
    (net (code "131") (name "unconnected-(NC5-Pad2)") (class "Default")
      (node (ref "NC5") (pin "2") (pinfunction "2_2") (pintype "passive"))
    )
    (net (code "132") (name "unconnected-(NC6-Pad1)") (class "Default")
      (node (ref "NC6") (pin "1") (pinfunction "1_1") (pintype "passive"))
    )
    (net (code "133") (name "unconnected-(NC6-Pad2)") (class "Default")
      (node (ref "NC6") (pin "2") (pinfunction "2_2") (pintype "passive"))
    )
    (net (code "134") (name "unconnected-(NC7-Pad1)") (class "Default")
      (node (ref "NC7") (pin "1") (pinfunction "1_1") (pintype "passive"))
    )
    (net (code "135") (name "unconnected-(NC7-Pad2)") (class "Default")
      (node (ref "NC7") (pin "2") (pinfunction "2_2") (pintype "passive"))
    )
    (net (code "136") (name "unconnected-(NC8-Pad1)") (class "Default")
      (node (ref "NC8") (pin "1") (pinfunction "1_1") (pintype "passive"))
    )
    (net (code "137") (name "unconnected-(U6-NC-Pad34)") (class "Default")
      (node (ref "U6") (pin "34") (pinfunction "NC_34") (pintype "no_connect"))
    )
    (net (code "138") (name "unconnected-(U6-NC_2-Pad24)") (class "Default")
      (node (ref "U6") (pin "24") (pinfunction "NC_2_24") (pintype "no_connect"))
    )
    (net (code "139") (name "unconnected-(U6-NC_3-Pad25)") (class "Default")
      (node (ref "U6") (pin "25") (pinfunction "NC_3_25") (pintype "no_connect"))
    )
    (net (code "140") (name "unconnected-(U6-NC_4-Pad26)") (class "Default")
      (node (ref "U6") (pin "26") (pinfunction "NC_4_26") (pintype "no_connect"))
    )
    (net (code "141") (name "unconnected-(U7-NC-Pad34)") (class "Default")
      (node (ref "U7") (pin "34") (pinfunction "NC_34") (pintype "no_connect"))
    )
    (net (code "142") (name "unconnected-(U7-NC_2-Pad24)") (class "Default")
      (node (ref "U7") (pin "24") (pinfunction "NC_2_24") (pintype "no_connect"))
    )
    (net (code "143") (name "unconnected-(U7-NC_3-Pad25)") (class "Default")
      (node (ref "U7") (pin "25") (pinfunction "NC_3_25") (pintype "no_connect"))
    )
    (net (code "144") (name "unconnected-(U7-NC_4-Pad26)") (class "Default")
      (node (ref "U7") (pin "26") (pinfunction "NC_4_26") (pintype "no_connect"))
    )
    (net (code "145") (name "unconnected-(U8-DATAOUT-Pad23)") (class "Default")
      (node (ref "U8") (pin "23") (pinfunction "DATAOUT_23") (pintype "output"))
    )
    (net (code "146") (name "unconnected-(U8-NC-Pad34)") (class "Default")
      (node (ref "U8") (pin "34") (pinfunction "NC_34") (pintype "no_connect"))
    )
    (net (code "147") (name "unconnected-(U8-NC_2-Pad24)") (class "Default")
      (node (ref "U8") (pin "24") (pinfunction "NC_2_24") (pintype "no_connect"))
    )
    (net (code "148") (name "unconnected-(U8-NC_3-Pad25)") (class "Default")
      (node (ref "U8") (pin "25") (pinfunction "NC_3_25") (pintype "no_connect"))
    )
    (net (code "149") (name "unconnected-(U8-NC_4-Pad26)") (class "Default")
      (node (ref "U8") (pin "26") (pinfunction "NC_4_26") (pintype "no_connect"))
    )
  )
)
